# MCU.net
KiCad netlist of a schematic drawn in Altium Designer
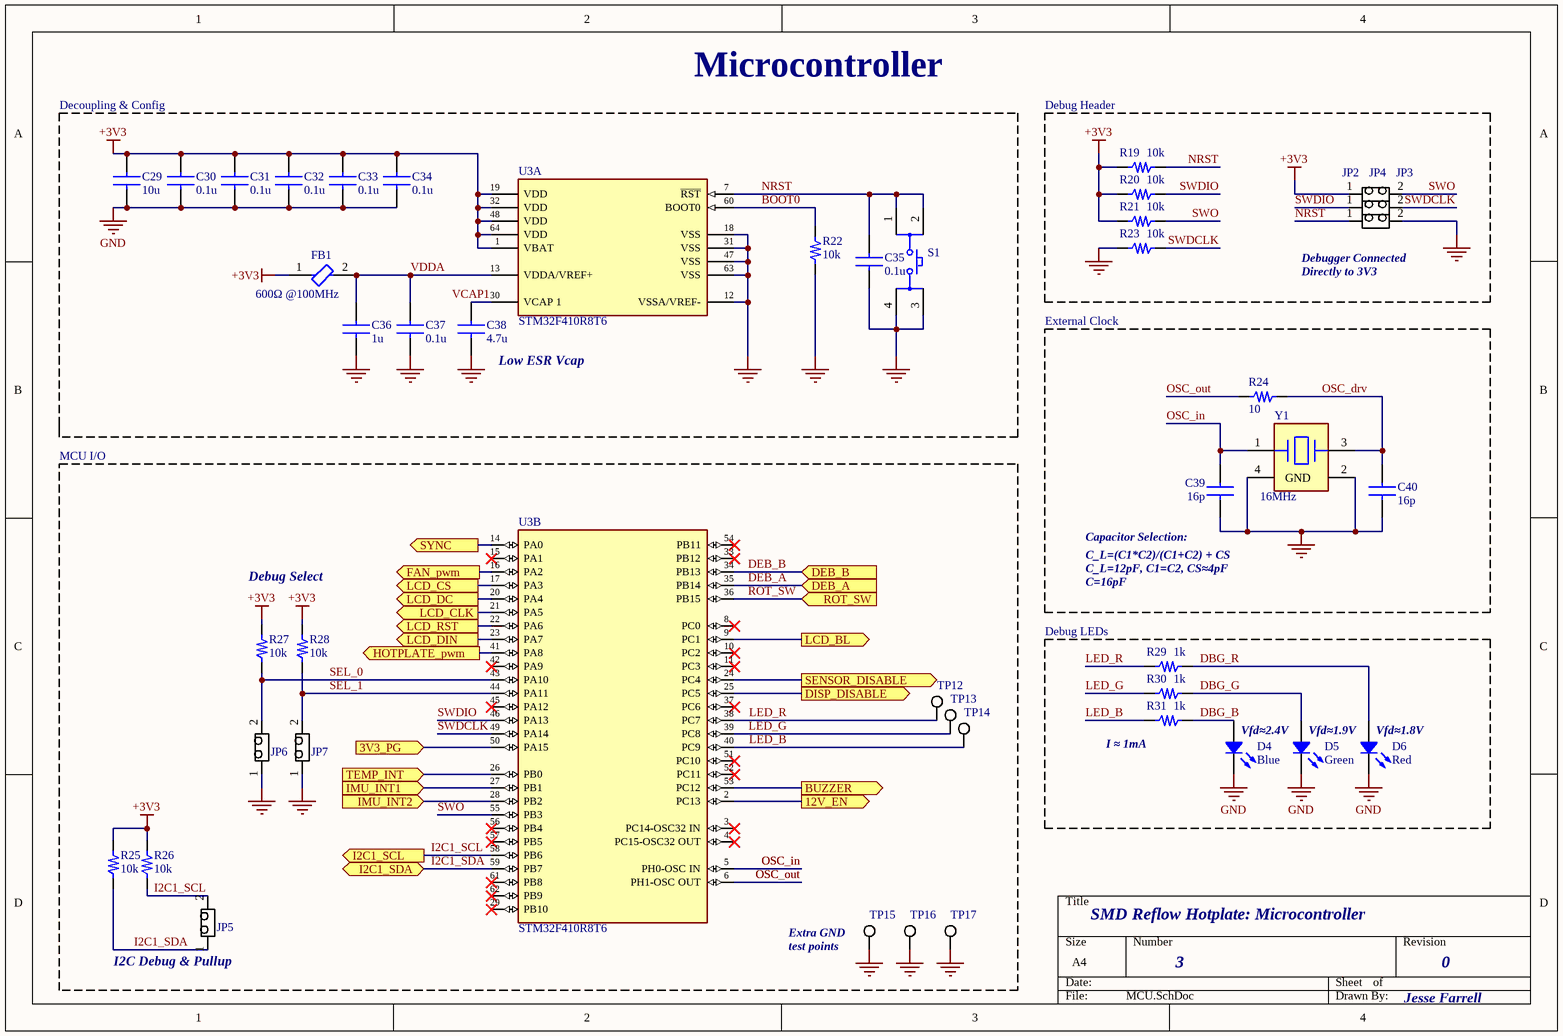
[diagram p0: MCU.SchDoc]

(export (version "E")
  (design (tool "Eeschema 10.0.6"))
  (components
    (comp (ref "C29")
      (value "10u")
      (footprint "FP-CL10-IPC_C")
      (description "Cap Ceramic 10uF 16V X5R 10% SMD 0603")
      (fields (field (name "TOLERANCE") "10%"))
      (libsource (lib "Schlib1") (part "CapTemplate0603"))
    )
    (comp (ref "C30")
      (value "0.1u")
      (footprint "FP-CL10-IPC_C")
      (description "Cap Ceramic 0.1uF 16V X7R 10% SMD 0603")
      (fields (field (name "TOLERANCE") "10%"))
      (libsource (lib "Schlib1") (part "CapTemplate0603"))
    )
    (comp (ref "C31")
      (value "0.1u")
      (footprint "FP-CL10-IPC_C")
      (description "Cap Ceramic 0.1uF 16V X7R 10% SMD 0603")
      (fields (field (name "TOLERANCE") "10%"))
      (libsource (lib "Schlib1") (part "CapTemplate0603"))
    )
    (comp (ref "C32")
      (value "0.1u")
      (footprint "FP-CL10-IPC_C")
      (description "Cap Ceramic 0.1uF 16V X7R 10% SMD 0603")
      (fields (field (name "TOLERANCE") "10%"))
      (libsource (lib "Schlib1") (part "CapTemplate0603"))
    )
    (comp (ref "C33")
      (value "0.1u")
      (footprint "FP-CL10-IPC_C")
      (description "Cap Ceramic 0.1uF 16V X7R 10% SMD 0603")
      (fields (field (name "TOLERANCE") "10%"))
      (libsource (lib "Schlib1") (part "CapTemplate0603"))
    )
    (comp (ref "C34")
      (value "0.1u")
      (footprint "FP-CL10-IPC_C")
      (description "Cap Ceramic 0.1uF 16V X7R 10% SMD 0603")
      (fields (field (name "TOLERANCE") "10%"))
      (libsource (lib "Schlib1") (part "CapTemplate0603"))
    )
    (comp (ref "C35")
      (value "0.1u")
      (footprint "FP-CL10-IPC_C")
      (description "Cap Ceramic 0.1uF 16V X7R 10% SMD 0603")
      (fields (field (name "TOLERANCE") "10%"))
      (libsource (lib "Schlib1") (part "CapTemplate0603"))
    )
    (comp (ref "C36")
      (value "1u")
      (footprint "FP-CL10-IPC_C")
      (description "Cap Ceramic 1uF 16V X5R 10% SMD 0603")
      (fields (field (name "TOLERANCE") "10%"))
      (libsource (lib "Schlib1") (part "CapTemplate0603"))
    )
    (comp (ref "C37")
      (value "0.1u")
      (footprint "FP-CL10-IPC_C")
      (description "Cap Ceramic 0.1uF 16V X7R 10% SMD 0603")
      (fields (field (name "TOLERANCE") "10%"))
      (libsource (lib "Schlib1") (part "CapTemplate0603"))
    )
    (comp (ref "C38")
      (value "4.7u")
      (footprint "FP-CL10-IPC_C")
      (description "Cap Ceramic 4.7uF 16V X5R 10% SMD 0603")
      (fields (field (name "TOLERANCE") "10%"))
      (libsource (lib "Schlib1") (part "CapTemplate0603"))
    )
    (comp (ref "C39")
      (value "16p")
      (footprint "FP-CL10-IPC_C")
      (description "Cap Ceramic 16p 10V X7R 10% SMD 0603")
      (fields (field (name "TOLERANCE") "??%"))
      (libsource (lib "Schlib1") (part "CapTemplate0603"))
    )
    (comp (ref "C40")
      (value "16p")
      (footprint "FP-CL10-IPC_C")
      (description "Cap Ceramic 16p 10V X7R 10% SMD 0603")
      (fields (field (name "TOLERANCE") "??%"))
      (libsource (lib "Schlib1") (part "CapTemplate0603"))
    )
    (comp (ref "D4")
      (value "Blue")
      (footprint "LED 0603_1608 BLUE")
      (description "1.6X0.8MM BLUE SMD LED")
      (fields (field (name "PART NUMBER") "AA1608QBS/D-10MAV") (field (name "MANUFACTURER") "Kingbright"))
      (libsource (lib "Celestial Altium Library - altium_library") (part "LED"))
    )
    (comp (ref "D5")
      (value "Green")
      (footprint "LED 0603_1608 GREEN")
      (description "1.6X0.8MM GREEN SMD LED")
      (fields (field (name "PART NUMBER") "AA1608CGSK") (field (name "MANUFACTURER") "Kingbright"))
      (libsource (lib "Celestial Altium Library - altium_library") (part "LED"))
    )
    (comp (ref "D6")
      (value "Red")
      (footprint "LED 0603_1608 RED")
      (description "1.6X0.8MM RED SMD LED")
      (fields (field (name "PART NUMBER") "AA1608SURSK") (field (name "MANUFACTURER") "Kingbright"))
      (libsource (lib "Celestial Altium Library - altium_library") (part "LED"))
    )
    (comp (ref "FB1")
      (value "600Ω @100MHz")
      (footprint "FP-BLM18-0_15-t0_8-MFG")
      (description "Ferrite Bead, Aec-Q200, 600 Ohm, 0603 Rohs Compliant: Yes")
      (fields
        (field (name "MANUFACTURER") "Wurth Electronics")
        (field (name "MANUFACTURER PART NUMBER") "782633601")
      )
      (libsource (lib "Schlib1") (part "782633601"))
    )
    (comp (ref "JP2")
      (value "HDR_1x2")
      (footprint "FP-TSW-102-07-L-S-MFG")
      (description "Conn Unshrouded Header HDR 2 POS 2.54mm Solder ST Thru-Hole Bag")
      (fields
        (field (name "MANUFACTURER") "Adam Equipment")
        (field (name "MANUFACTURER PART NUMBER") "PH1-02-UA")
      )
      (libsource (lib "Schlib1") (part "PH1-02-UA"))
    )
    (comp (ref "JP3")
      (value "HDR_1x2")
      (footprint "FP-TSW-102-07-L-S-MFG")
      (description "Conn Unshrouded Header HDR 2 POS 2.54mm Solder ST Thru-Hole Bag")
      (fields
        (field (name "MANUFACTURER") "Adam Equipment")
        (field (name "MANUFACTURER PART NUMBER") "PH1-02-UA")
      )
      (libsource (lib "Schlib1") (part "PH1-02-UA"))
    )
    (comp (ref "JP4")
      (value "HDR_1x2")
      (footprint "FP-TSW-102-07-L-S-MFG")
      (description "Conn Unshrouded Header HDR 2 POS 2.54mm Solder ST Thru-Hole Bag")
      (fields
        (field (name "MANUFACTURER") "Adam Equipment")
        (field (name "MANUFACTURER PART NUMBER") "PH1-02-UA")
      )
      (libsource (lib "Schlib1") (part "PH1-02-UA"))
    )
    (comp (ref "JP5")
      (value "HDR_1x2")
      (footprint "FP-TSW-102-07-L-S-MFG")
      (description "Conn Unshrouded Header HDR 2 POS 2.54mm Solder ST Thru-Hole Bag")
      (fields
        (field (name "MANUFACTURER") "Adam Equipment")
        (field (name "MANUFACTURER PART NUMBER") "PH1-02-UA")
      )
      (libsource (lib "Schlib1") (part "PH1-02-UA"))
    )
    (comp (ref "JP6")
      (value "HDR_1x2")
      (footprint "FP-TSW-102-07-L-S-MFG")
      (description "Conn Unshrouded Header HDR 2 POS 2.54mm Solder ST Thru-Hole Bag")
      (fields
        (field (name "MANUFACTURER") "Adam Equipment")
        (field (name "MANUFACTURER PART NUMBER") "PH1-02-UA")
      )
      (libsource (lib "Schlib1") (part "PH1-02-UA"))
    )
    (comp (ref "JP7")
      (value "HDR_1x2")
      (footprint "FP-TSW-102-07-L-S-MFG")
      (description "Conn Unshrouded Header HDR 2 POS 2.54mm Solder ST Thru-Hole Bag")
      (fields
        (field (name "MANUFACTURER") "Adam Equipment")
        (field (name "MANUFACTURER PART NUMBER") "PH1-02-UA")
      )
      (libsource (lib "Schlib1") (part "PH1-02-UA"))
    )
    (comp (ref "R19")
      (value "10k")
      (footprint "FP-RMCF0603-MFG")
      (description "Res 0603 10K Ohm 1% 1/10W")
      (fields (field (name "TOLERANCE") "???%"))
      (libsource (lib "Schlib1") (part "ResTemplate0603"))
    )
    (comp (ref "R20")
      (value "10k")
      (footprint "FP-RMCF0603-MFG")
      (description "Res 0603 10K Ohm 1% 1/10W")
      (fields (field (name "TOLERANCE") "???%"))
      (libsource (lib "Schlib1") (part "ResTemplate0603"))
    )
    (comp (ref "R21")
      (value "10k")
      (footprint "FP-RMCF0603-MFG")
      (description "Res 0603 10K Ohm 1% 1/10W")
      (fields (field (name "TOLERANCE") "???%"))
      (libsource (lib "Schlib1") (part "ResTemplate0603"))
    )
    (comp (ref "R22")
      (value "10k")
      (footprint "FP-RMCF0603-MFG")
      (description "Res 0603 10K Ohm 1% 1/10W")
      (fields (field (name "TOLERANCE") "???%"))
      (libsource (lib "Schlib1") (part "ResTemplate0603"))
    )
    (comp (ref "R23")
      (value "10k")
      (footprint "FP-RMCF0603-MFG")
      (description "Res 0603 10K Ohm 1% 1/10W")
      (fields (field (name "TOLERANCE") "???%"))
      (libsource (lib "Schlib1") (part "ResTemplate0603"))
    )
    (comp (ref "R24")
      (value "10")
      (footprint "FP-RMCF0603-MFG")
      (description "Res 0603 10 Ohm 1% 1/10W")
      (fields (field (name "TOLERANCE") "???%"))
      (libsource (lib "Schlib1") (part "ResTemplate0603"))
    )
    (comp (ref "R25")
      (value "10k")
      (footprint "FP-RMCF0603-MFG")
      (description "Res 0603 10K Ohm 1% 1/10W")
      (fields (field (name "TOLERANCE") "???%"))
      (libsource (lib "Schlib1") (part "ResTemplate0603"))
    )
    (comp (ref "R26")
      (value "10k")
      (footprint "FP-RMCF0603-MFG")
      (description "Res 0603 10K Ohm 1% 1/10W")
      (fields (field (name "TOLERANCE") "???%"))
      (libsource (lib "Schlib1") (part "ResTemplate0603"))
    )
    (comp (ref "R27")
      (value "10k")
      (footprint "FP-RMCF0603-MFG")
      (description "Res 0603 10K Ohm 1% 1/10W")
      (fields (field (name "TOLERANCE") "???%"))
      (libsource (lib "Schlib1") (part "ResTemplate0603"))
    )
    (comp (ref "R28")
      (value "10k")
      (footprint "FP-RMCF0603-MFG")
      (description "Res 0603 10K Ohm 1% 1/10W")
      (fields (field (name "TOLERANCE") "???%"))
      (libsource (lib "Schlib1") (part "ResTemplate0603"))
    )
    (comp (ref "R29")
      (value "1k")
      (footprint "FP-RMCF0603-MFG")
      (description "Res 0603 1K Ohm 1% 1/8W")
      (fields (field (name "TOLERANCE") "???%"))
      (libsource (lib "Schlib1") (part "ResTemplate0603"))
    )
    (comp (ref "R30")
      (value "1k")
      (footprint "FP-RMCF0603-MFG")
      (description "Res 0603 1K Ohm 1% 1/8W")
      (fields (field (name "TOLERANCE") "???%"))
      (libsource (lib "Schlib1") (part "ResTemplate0603"))
    )
    (comp (ref "R31")
      (value "1k")
      (footprint "FP-RMCF0603-MFG")
      (description "Res 0603 1K Ohm 1% 1/8W")
      (fields (field (name "TOLERANCE") "???%"))
      (libsource (lib "Schlib1") (part "ResTemplate0603"))
    )
    (comp (ref "S1")
      (value "PushButton")
      (footprint "FP-TL3301AF160QG-MFG")
      (description "Switch Tactile N.O. SPST Round Button Gull Wing 0.05A 12VDC 100000Cycles 1.27N SMD T/R")
      (fields
        (field (name "MANUFACTURER") "ITT C&K")
        (field (name "MANUFACTURER PART NUMBER") "PTS645SL43SMTR92LFS")
      )
      (libsource (lib "Schlib1") (part "PTS645SL43SMTR92LFS"))
    )
    (comp (ref "TP12")
      (value "TEST POINT")
      (footprint "KSTN-5003")
      (description "Test Point;  Miniature;  THM;  H .300;  Nylon 46 Insulated Orange;  PhosBronze/Silver")
      (fields
        (field (name "MANUFACTURER") "Keystone Electronics")
        (field (name "MANUFACTURER PART NUMBER") "5003")
      )
      (libsource (lib "Schlib1") (part "5003"))
    )
    (comp (ref "TP13")
      (value "TEST POINT")
      (footprint "KSTN-5003")
      (description "Test Point;  Miniature;  THM;  H .300;  Nylon 46 Insulated Orange;  PhosBronze/Silver")
      (fields
        (field (name "MANUFACTURER") "Keystone Electronics")
        (field (name "MANUFACTURER PART NUMBER") "5003")
      )
      (libsource (lib "Schlib1") (part "5003"))
    )
    (comp (ref "TP14")
      (value "TEST POINT")
      (footprint "KSTN-5003")
      (description "Test Point;  Miniature;  THM;  H .300;  Nylon 46 Insulated Orange;  PhosBronze/Silver")
      (fields
        (field (name "MANUFACTURER") "Keystone Electronics")
        (field (name "MANUFACTURER PART NUMBER") "5003")
      )
      (libsource (lib "Schlib1") (part "5003"))
    )
    (comp (ref "TP15")
      (value "BLCK TEST POINT")
      (footprint "FP-5001-MFG")
      (description "TEST POINT PC MINI .040D BLACK")
      (fields
        (field (name "MANUFACTURER") "Keystone Electronics")
        (field (name "MANUFACTURER PART NUMBER") "5001")
      )
      (libsource (lib "Schlib1") (part "5001"))
    )
    (comp (ref "TP16")
      (value "BLCK TEST POINT")
      (footprint "FP-5001-MFG")
      (description "TEST POINT PC MINI .040D BLACK")
      (fields
        (field (name "MANUFACTURER") "Keystone Electronics")
        (field (name "MANUFACTURER PART NUMBER") "5001")
      )
      (libsource (lib "Schlib1") (part "5001"))
    )
    (comp (ref "TP17")
      (value "BLCK TEST POINT")
      (footprint "FP-5001-MFG")
      (description "TEST POINT PC MINI .040D BLACK")
      (fields
        (field (name "MANUFACTURER") "Keystone Electronics")
        (field (name "MANUFACTURER PART NUMBER") "5001")
      )
      (libsource (lib "Schlib1") (part "5001"))
    )
    (comp (ref "U3")
      (value "STM32F410R8T6")
      (footprint "FP-LQFP64-5W-IPC_B")
      (description "MCU 32-bit ARM Cortex M4 RISC 64KB Flash 3.3V 64-Pin LQFP Frame")
      (fields (field (name "MANUFACTURER") "STMicroelectronics"))
      (libsource (lib "Schlib1") (part "STM32F410R8T6"))
    )
    (comp (ref "Y1")
      (value "16MHz")
      (footprint "FP-8Y-MFG")
      (description "Crystal Template for 4-SMD Crystal")
      (libsource (lib "Schlib1") (part "Crystal_Template"))
    )
  )
  (nets
    (net (code "1") (name "+3V3") (class "Default")
      (node (ref "C29") (pin "1") (pinfunction "1_1") (pintype "passive"))
      (node (ref "C30") (pin "1") (pinfunction "1_1") (pintype "passive"))
      (node (ref "C31") (pin "1") (pinfunction "1_1") (pintype "passive"))
      (node (ref "C32") (pin "1") (pinfunction "1_1") (pintype "passive"))
      (node (ref "C33") (pin "1") (pinfunction "1_1") (pintype "passive"))
      (node (ref "C34") (pin "1") (pinfunction "1_1") (pintype "passive"))
      (node (ref "FB1") (pin "1") (pinfunction "1_1") (pintype "passive"))
      (node (ref "JP2") (pin "1") (pinfunction "1_1") (pintype "passive"))
      (node (ref "R19") (pin "2") (pinfunction "2_2") (pintype "passive"))
      (node (ref "R20") (pin "2") (pinfunction "2_2") (pintype "passive"))
      (node (ref "R21") (pin "2") (pinfunction "2_2") (pintype "passive"))
      (node (ref "R25") (pin "2") (pinfunction "2_2") (pintype "passive"))
      (node (ref "R26") (pin "2") (pinfunction "2_2") (pintype "passive"))
      (node (ref "R27") (pin "2") (pinfunction "2_2") (pintype "passive"))
      (node (ref "R28") (pin "2") (pinfunction "2_2") (pintype "passive"))
      (node (ref "U3") (pin "1") (pinfunction "VBAT_1") (pintype "power_in"))
      (node (ref "U3") (pin "19") (pinfunction "VDD_19") (pintype "power_in"))
      (node (ref "U3") (pin "32") (pinfunction "VDD_32") (pintype "power_in"))
      (node (ref "U3") (pin "48") (pinfunction "VDD_48") (pintype "power_in"))
      (node (ref "U3") (pin "64") (pinfunction "VDD_64") (pintype "power_in"))
    )
    (net (code "2") (name "/3V3_PG") (class "Default")
      (node (ref "U3") (pin "50") (pinfunction "PA15_50") (pintype "bidirectional"))
    )
    (net (code "3") (name "/12V_EN") (class "Default")
      (node (ref "U3") (pin "2") (pinfunction "PC13_2") (pintype "bidirectional"))
    )
    (net (code "4") (name "/BOOT0") (class "Default")
      (node (ref "R22") (pin "2") (pinfunction "2_2") (pintype "passive"))
      (node (ref "U3") (pin "60") (pinfunction "BOOT0_60") (pintype "input"))
    )
    (net (code "5") (name "/BUZZER") (class "Default")
      (node (ref "U3") (pin "53") (pinfunction "PC12_53") (pintype "bidirectional"))
    )
    (net (code "6") (name "/DBG_B") (class "Default")
      (node (ref "D4") (pin "1") (pinfunction "1_1") (pintype "passive"))
      (node (ref "R31") (pin "1") (pinfunction "1_1") (pintype "passive"))
    )
    (net (code "7") (name "/DBG_G") (class "Default")
      (node (ref "D5") (pin "1") (pinfunction "1_1") (pintype "passive"))
      (node (ref "R30") (pin "1") (pinfunction "1_1") (pintype "passive"))
    )
    (net (code "8") (name "/DBG_R") (class "Default")
      (node (ref "D6") (pin "1") (pinfunction "1_1") (pintype "passive"))
      (node (ref "R29") (pin "1") (pinfunction "1_1") (pintype "passive"))
    )
    (net (code "9") (name "/DEB_A") (class "Default")
      (node (ref "U3") (pin "35") (pinfunction "PB14_35") (pintype "bidirectional"))
    )
    (net (code "10") (name "/DEB_B") (class "Default")
      (node (ref "U3") (pin "34") (pinfunction "PB13_34") (pintype "bidirectional"))
    )
    (net (code "11") (name "/DISP_DISABLE") (class "Default")
      (node (ref "U3") (pin "25") (pinfunction "PC5_25") (pintype "bidirectional"))
    )
    (net (code "12") (name "/FAN_pwm") (class "Default")
      (node (ref "U3") (pin "16") (pinfunction "PA2_16") (pintype "bidirectional"))
    )
    (net (code "13") (name "/HOTPLATE_pwm") (class "Default")
      (node (ref "U3") (pin "41") (pinfunction "PA8_41") (pintype "bidirectional"))
    )
    (net (code "14") (name "/I2C1_SCL") (class "Default")
      (node (ref "JP5") (pin "2") (pinfunction "2_2") (pintype "passive"))
      (node (ref "R26") (pin "1") (pinfunction "1_1") (pintype "passive"))
      (node (ref "U3") (pin "58") (pinfunction "PB6_58") (pintype "bidirectional"))
    )
    (net (code "15") (name "/I2C1_SDA") (class "Default")
      (node (ref "JP5") (pin "1") (pinfunction "1_1") (pintype "passive"))
      (node (ref "R25") (pin "1") (pinfunction "1_1") (pintype "passive"))
      (node (ref "U3") (pin "59") (pinfunction "PB7_59") (pintype "bidirectional"))
    )
    (net (code "16") (name "/IMU_INT1") (class "Default")
      (node (ref "U3") (pin "27") (pinfunction "PB1_27") (pintype "bidirectional"))
    )
    (net (code "17") (name "/IMU_INT2") (class "Default")
      (node (ref "U3") (pin "28") (pinfunction "PB2_28") (pintype "bidirectional"))
    )
    (net (code "18") (name "/LCD_BL") (class "Default")
      (node (ref "U3") (pin "9") (pinfunction "PC1_9") (pintype "bidirectional"))
    )
    (net (code "19") (name "/LCD_CLK") (class "Default")
      (node (ref "U3") (pin "21") (pinfunction "PA5_21") (pintype "bidirectional"))
    )
    (net (code "20") (name "/LCD_CS") (class "Default")
      (node (ref "U3") (pin "17") (pinfunction "PA3_17") (pintype "bidirectional"))
    )
    (net (code "21") (name "/LCD_DC") (class "Default")
      (node (ref "U3") (pin "20") (pinfunction "PA4_20") (pintype "bidirectional"))
    )
    (net (code "22") (name "/LCD_DIN") (class "Default")
      (node (ref "U3") (pin "23") (pinfunction "PA7_23") (pintype "bidirectional"))
    )
    (net (code "23") (name "/LCD_RST") (class "Default")
      (node (ref "U3") (pin "22") (pinfunction "PA6_22") (pintype "bidirectional"))
    )
    (net (code "24") (name "/LED_B") (class "Default")
      (node (ref "R31") (pin "2") (pinfunction "2_2") (pintype "passive"))
      (node (ref "TP14") (pin "1") (pinfunction "1_1") (pintype "passive"))
      (node (ref "U3") (pin "40") (pinfunction "PC9_40") (pintype "bidirectional"))
    )
    (net (code "25") (name "/LED_G") (class "Default")
      (node (ref "R30") (pin "2") (pinfunction "2_2") (pintype "passive"))
      (node (ref "TP13") (pin "1") (pinfunction "1_1") (pintype "passive"))
      (node (ref "U3") (pin "39") (pinfunction "PC8_39") (pintype "bidirectional"))
    )
    (net (code "26") (name "/LED_R") (class "Default")
      (node (ref "R29") (pin "2") (pinfunction "2_2") (pintype "passive"))
      (node (ref "TP12") (pin "1") (pinfunction "1_1") (pintype "passive"))
      (node (ref "U3") (pin "38") (pinfunction "PC7_38") (pintype "bidirectional"))
    )
    (net (code "27") (name "/NRST") (class "Default")
      (node (ref "C35") (pin "1") (pinfunction "1_1") (pintype "passive"))
      (node (ref "JP4") (pin "1") (pinfunction "1_1") (pintype "passive"))
      (node (ref "R19") (pin "1") (pinfunction "1_1") (pintype "passive"))
      (node (ref "S1") (pin "1") (pinfunction "1_1") (pintype "passive"))
      (node (ref "S1") (pin "2") (pinfunction "2_2") (pintype "passive"))
      (node (ref "U3") (pin "7") (pinfunction "~{RST}_7") (pintype "input"))
    )
    (net (code "28") (name "/OSC_drv") (class "Default")
      (node (ref "C40") (pin "1") (pinfunction "1_1") (pintype "passive"))
      (node (ref "R24") (pin "1") (pinfunction "1_1") (pintype "passive"))
      (node (ref "Y1") (pin "3") (pinfunction "3_3") (pintype "passive"))
    )
    (net (code "29") (name "/OSC_in") (class "Default")
      (node (ref "C39") (pin "1") (pinfunction "1_1") (pintype "passive"))
      (node (ref "U3") (pin "5") (pinfunction "PH0-OSC_IN_5") (pintype "bidirectional"))
      (node (ref "Y1") (pin "1") (pinfunction "1_1") (pintype "passive"))
    )
    (net (code "30") (name "/OSC_out") (class "Default")
      (node (ref "R24") (pin "2") (pinfunction "2_2") (pintype "passive"))
      (node (ref "U3") (pin "6") (pinfunction "PH1-OSC_OUT_6") (pintype "bidirectional"))
    )
    (net (code "31") (name "/ROT_SW") (class "Default")
      (node (ref "U3") (pin "36") (pinfunction "PB15_36") (pintype "bidirectional"))
    )
    (net (code "32") (name "/SEL_0") (class "Default")
      (node (ref "JP6") (pin "2") (pinfunction "2_2") (pintype "passive"))
      (node (ref "R27") (pin "1") (pinfunction "1_1") (pintype "passive"))
      (node (ref "U3") (pin "43") (pinfunction "PA10_43") (pintype "bidirectional"))
    )
    (net (code "33") (name "/SEL_1") (class "Default")
      (node (ref "JP7") (pin "2") (pinfunction "2_2") (pintype "passive"))
      (node (ref "R28") (pin "1") (pinfunction "1_1") (pintype "passive"))
      (node (ref "U3") (pin "44") (pinfunction "PA11_44") (pintype "bidirectional"))
    )
    (net (code "34") (name "/SENSOR_DISABLE") (class "Default")
      (node (ref "U3") (pin "24") (pinfunction "PC4_24") (pintype "bidirectional"))
    )
    (net (code "35") (name "/SWDCLK") (class "Default")
      (node (ref "JP3") (pin "2") (pinfunction "2_2") (pintype "passive"))
      (node (ref "R23") (pin "1") (pinfunction "1_1") (pintype "passive"))
      (node (ref "U3") (pin "49") (pinfunction "PA14_49") (pintype "bidirectional"))
    )
    (net (code "36") (name "/SWDIO") (class "Default")
      (node (ref "JP3") (pin "1") (pinfunction "1_1") (pintype "passive"))
      (node (ref "R20") (pin "1") (pinfunction "1_1") (pintype "passive"))
      (node (ref "U3") (pin "46") (pinfunction "PA13_46") (pintype "bidirectional"))
    )
    (net (code "37") (name "/SWO") (class "Default")
      (node (ref "JP2") (pin "2") (pinfunction "2_2") (pintype "passive"))
      (node (ref "R21") (pin "1") (pinfunction "1_1") (pintype "passive"))
      (node (ref "U3") (pin "55") (pinfunction "PB3_55") (pintype "bidirectional"))
    )
    (net (code "38") (name "/SYNC") (class "Default")
      (node (ref "U3") (pin "14") (pinfunction "PA0_14") (pintype "bidirectional"))
    )
    (net (code "39") (name "/TEMP_INT") (class "Default")
      (node (ref "U3") (pin "26") (pinfunction "PB0_26") (pintype "bidirectional"))
    )
    (net (code "40") (name "/VCAP1") (class "Default")
      (node (ref "C38") (pin "1") (pinfunction "1_1") (pintype "passive"))
      (node (ref "U3") (pin "30") (pinfunction "VCAP_1_30") (pintype "power_in"))
    )
    (net (code "41") (name "/VDDA") (class "Default")
      (node (ref "C36") (pin "1") (pinfunction "1_1") (pintype "passive"))
      (node (ref "C37") (pin "1") (pinfunction "1_1") (pintype "passive"))
      (node (ref "FB1") (pin "2") (pinfunction "2_2") (pintype "passive"))
      (node (ref "U3") (pin "13") (pinfunction "VDDA/VREF+_13") (pintype "power_in"))
    )
    (net (code "42") (name "GND") (class "Default")
      (node (ref "C29") (pin "2") (pinfunction "2_2") (pintype "passive"))
      (node (ref "C30") (pin "2") (pinfunction "2_2") (pintype "passive"))
      (node (ref "C31") (pin "2") (pinfunction "2_2") (pintype "passive"))
      (node (ref "C32") (pin "2") (pinfunction "2_2") (pintype "passive"))
      (node (ref "C33") (pin "2") (pinfunction "2_2") (pintype "passive"))
      (node (ref "C34") (pin "2") (pinfunction "2_2") (pintype "passive"))
      (node (ref "C35") (pin "2") (pinfunction "2_2") (pintype "passive"))
      (node (ref "C36") (pin "2") (pinfunction "2_2") (pintype "passive"))
      (node (ref "C37") (pin "2") (pinfunction "2_2") (pintype "passive"))
      (node (ref "C38") (pin "2") (pinfunction "2_2") (pintype "passive"))
      (node (ref "C39") (pin "2") (pinfunction "2_2") (pintype "passive"))
      (node (ref "C40") (pin "2") (pinfunction "2_2") (pintype "passive"))
      (node (ref "D4") (pin "2") (pinfunction "2_2") (pintype "passive"))
      (node (ref "D5") (pin "2") (pinfunction "2_2") (pintype "passive"))
      (node (ref "D6") (pin "2") (pinfunction "2_2") (pintype "passive"))
      (node (ref "JP4") (pin "2") (pinfunction "2_2") (pintype "passive"))
      (node (ref "JP6") (pin "1") (pinfunction "1_1") (pintype "passive"))
      (node (ref "JP7") (pin "1") (pinfunction "1_1") (pintype "passive"))
      (node (ref "R22") (pin "1") (pinfunction "1_1") (pintype "passive"))
      (node (ref "R23") (pin "2") (pinfunction "2_2") (pintype "passive"))
      (node (ref "S1") (pin "3") (pinfunction "3_3") (pintype "passive"))
      (node (ref "S1") (pin "4") (pinfunction "4_4") (pintype "passive"))
      (node (ref "TP15") (pin "1") (pinfunction "1_1") (pintype "passive"))
      (node (ref "TP16") (pin "1") (pinfunction "1_1") (pintype "passive"))
      (node (ref "TP17") (pin "1") (pinfunction "1_1") (pintype "passive"))
      (node (ref "U3") (pin "12") (pinfunction "VSSA/VREF-_12") (pintype "power_in"))
      (node (ref "U3") (pin "18") (pinfunction "VSS_18") (pintype "power_in"))
      (node (ref "U3") (pin "31") (pinfunction "VSS_31") (pintype "power_in"))
      (node (ref "U3") (pin "47") (pinfunction "VSS_47") (pintype "power_in"))
      (node (ref "U3") (pin "63") (pinfunction "VSS_63") (pintype "power_in"))
      (node (ref "Y1") (pin "2") (pinfunction "GND_2") (pintype "power_in"))
      (node (ref "Y1") (pin "4") (pinfunction "GND_4") (pintype "power_in"))
    )
    (net (code "43") (name "unconnected-(U3B-PA1-Pad15)") (class "Default")
      (node (ref "U3") (pin "15") (pinfunction "PA1_15") (pintype "bidirectional+no_connect"))
    )
    (net (code "44") (name "unconnected-(U3B-PA9-Pad42)") (class "Default")
      (node (ref "U3") (pin "42") (pinfunction "PA9_42") (pintype "bidirectional+no_connect"))
    )
    (net (code "45") (name "unconnected-(U3B-PA12-Pad45)") (class "Default")
      (node (ref "U3") (pin "45") (pinfunction "PA12_45") (pintype "bidirectional+no_connect"))
    )
    (net (code "46") (name "unconnected-(U3B-PB4-Pad56)") (class "Default")
      (node (ref "U3") (pin "56") (pinfunction "PB4_56") (pintype "bidirectional+no_connect"))
    )
    (net (code "47") (name "unconnected-(U3B-PB5-Pad57)") (class "Default")
      (node (ref "U3") (pin "57") (pinfunction "PB5_57") (pintype "bidirectional+no_connect"))
    )
    (net (code "48") (name "unconnected-(U3B-PB8-Pad61)") (class "Default")
      (node (ref "U3") (pin "61") (pinfunction "PB8_61") (pintype "bidirectional+no_connect"))
    )
    (net (code "49") (name "unconnected-(U3B-PB9-Pad62)") (class "Default")
      (node (ref "U3") (pin "62") (pinfunction "PB9_62") (pintype "bidirectional+no_connect"))
    )
    (net (code "50") (name "unconnected-(U3B-PB10-Pad29)") (class "Default")
      (node (ref "U3") (pin "29") (pinfunction "PB10_29") (pintype "bidirectional+no_connect"))
    )
    (net (code "51") (name "unconnected-(U3B-PB11-Pad54)") (class "Default")
      (node (ref "U3") (pin "54") (pinfunction "PB11_54") (pintype "bidirectional+no_connect"))
    )
    (net (code "52") (name "unconnected-(U3B-PB12-Pad33)") (class "Default")
      (node (ref "U3") (pin "33") (pinfunction "PB12_33") (pintype "bidirectional+no_connect"))
    )
    (net (code "53") (name "unconnected-(U3B-PC0-Pad8)") (class "Default")
      (node (ref "U3") (pin "8") (pinfunction "PC0_8") (pintype "bidirectional+no_connect"))
    )
    (net (code "54") (name "unconnected-(U3B-PC2-Pad10)") (class "Default")
      (node (ref "U3") (pin "10") (pinfunction "PC2_10") (pintype "bidirectional+no_connect"))
    )
    (net (code "55") (name "unconnected-(U3B-PC3-Pad11)") (class "Default")
      (node (ref "U3") (pin "11") (pinfunction "PC3_11") (pintype "bidirectional+no_connect"))
    )
    (net (code "56") (name "unconnected-(U3B-PC6-Pad37)") (class "Default")
      (node (ref "U3") (pin "37") (pinfunction "PC6_37") (pintype "bidirectional+no_connect"))
    )
    (net (code "57") (name "unconnected-(U3B-PC10-Pad51)") (class "Default")
      (node (ref "U3") (pin "51") (pinfunction "PC10_51") (pintype "bidirectional+no_connect"))
    )
    (net (code "58") (name "unconnected-(U3B-PC11-Pad52)") (class "Default")
      (node (ref "U3") (pin "52") (pinfunction "PC11_52") (pintype "bidirectional+no_connect"))
    )
    (net (code "59") (name "unconnected-(U3B-PC14-OSC32_IN-Pad3)") (class "Default")
      (node (ref "U3") (pin "3") (pinfunction "PC14-OSC32_IN_3") (pintype "bidirectional+no_connect"))
    )
    (net (code "60") (name "unconnected-(U3B-PC15-OSC32_OUT-Pad4)") (class "Default")
      (node (ref "U3") (pin "4") (pinfunction "PC15-OSC32_OUT_4") (pintype "bidirectional+no_connect"))
    )
  )
)
